# FlowSensor.net
KiCad netlist of a schematic drawn in Altium Designer
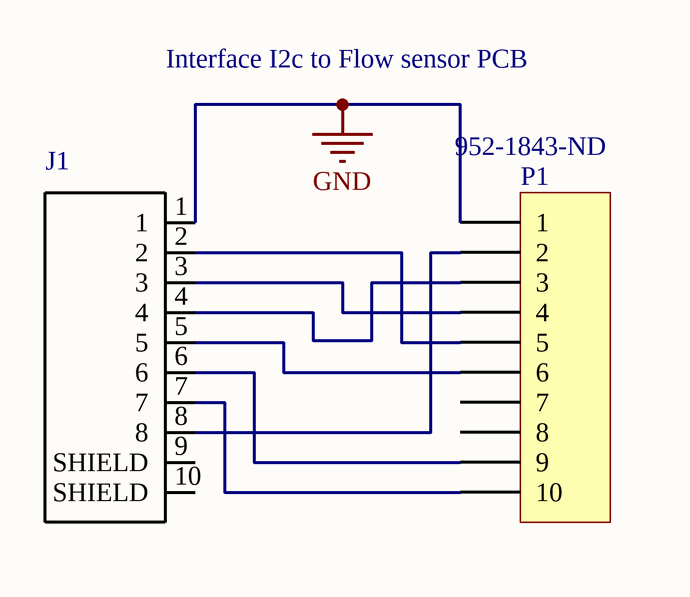
[diagram p0: FlowSensor.SchDoc]

(export (version "E")
  (design (tool "Eeschema 10.0.6"))
  (components
    (comp (ref "J1")
      (value "RJ45-8N-B")
      (footprint "TE_RJ45-8N-B")
      (description "Corcom; Filter; Signal Line; Modular; 8 Contacts; 1 Port Through Hole")
      (fields (field (name "MF") "TE Connectivity"))
      (libsource (lib "MOvIT-Detect PCB") (part "RJ45-8N-B"))
    )
    (comp (ref "P1")
      (value "~")
      (footprint "HDR1X10")
      (description "Header, 10-Pin")
      (fields
        (field (name "SUPPLIER PART NUMBER 1") "952-1843-ND")
        (field (name "PUBLISHER") "Altium Limited")
      )
      (libsource (lib "MOvIT-Detect PCB") (part "Header 10"))
    )
  )
  (nets
    (net (code "1") (name "GND") (class "Default")
      (node (ref "J1") (pin "1") (pinfunction "1_1") (pintype "passive"))
      (node (ref "P1") (pin "1") (pinfunction "1_1") (pintype "passive"))
    )
    (net (code "2") (name "Net-(J1-Pad2)") (class "Default")
      (node (ref "J1") (pin "2") (pinfunction "2_2") (pintype "passive"))
      (node (ref "P1") (pin "5") (pinfunction "5_5") (pintype "passive"))
    )
    (net (code "3") (name "Net-(J1-Pad3)") (class "Default")
      (node (ref "J1") (pin "3") (pinfunction "3_3") (pintype "passive"))
      (node (ref "P1") (pin "4") (pinfunction "4_4") (pintype "passive"))
    )
    (net (code "4") (name "Net-(J1-Pad4)") (class "Default")
      (node (ref "J1") (pin "4") (pinfunction "4_4") (pintype "passive"))
      (node (ref "P1") (pin "3") (pinfunction "3_3") (pintype "passive"))
    )
    (net (code "5") (name "Net-(J1-Pad5)") (class "Default")
      (node (ref "J1") (pin "5") (pinfunction "5_5") (pintype "passive"))
      (node (ref "P1") (pin "6") (pinfunction "6_6") (pintype "passive"))
    )
    (net (code "6") (name "Net-(J1-Pad6)") (class "Default")
      (node (ref "J1") (pin "6") (pinfunction "6_6") (pintype "passive"))
      (node (ref "P1") (pin "9") (pinfunction "9_9") (pintype "passive"))
    )
    (net (code "7") (name "Net-(J1-Pad7)") (class "Default")
      (node (ref "J1") (pin "7") (pinfunction "7_7") (pintype "passive"))
      (node (ref "P1") (pin "10") (pinfunction "10_10") (pintype "passive"))
    )
    (net (code "8") (name "Net-(J1-Pad8)") (class "Default")
      (node (ref "J1") (pin "8") (pinfunction "8_8") (pintype "passive"))
      (node (ref "P1") (pin "2") (pinfunction "2_2") (pintype "passive"))
    )
    (net (code "9") (name "unconnected-(J1-SHIELD-Pad9)") (class "Default")
      (node (ref "J1") (pin "9") (pinfunction "SHIELD_9") (pintype "passive"))
    )
    (net (code "10") (name "unconnected-(J1-SHIELD-Pad10)") (class "Default")
      (node (ref "J1") (pin "10") (pinfunction "SHIELD_10") (pintype "passive"))
    )
    (net (code "11") (name "unconnected-(P1-Pad7)") (class "Default")
      (node (ref "P1") (pin "7") (pinfunction "7_7") (pintype "passive"))
    )
    (net (code "12") (name "unconnected-(P1-Pad8)") (class "Default")
      (node (ref "P1") (pin "8") (pinfunction "8_8") (pintype "passive"))
    )
  )
)
